# PCB_Calc.net
KiCad netlist of a schematic drawn in Altium Designer
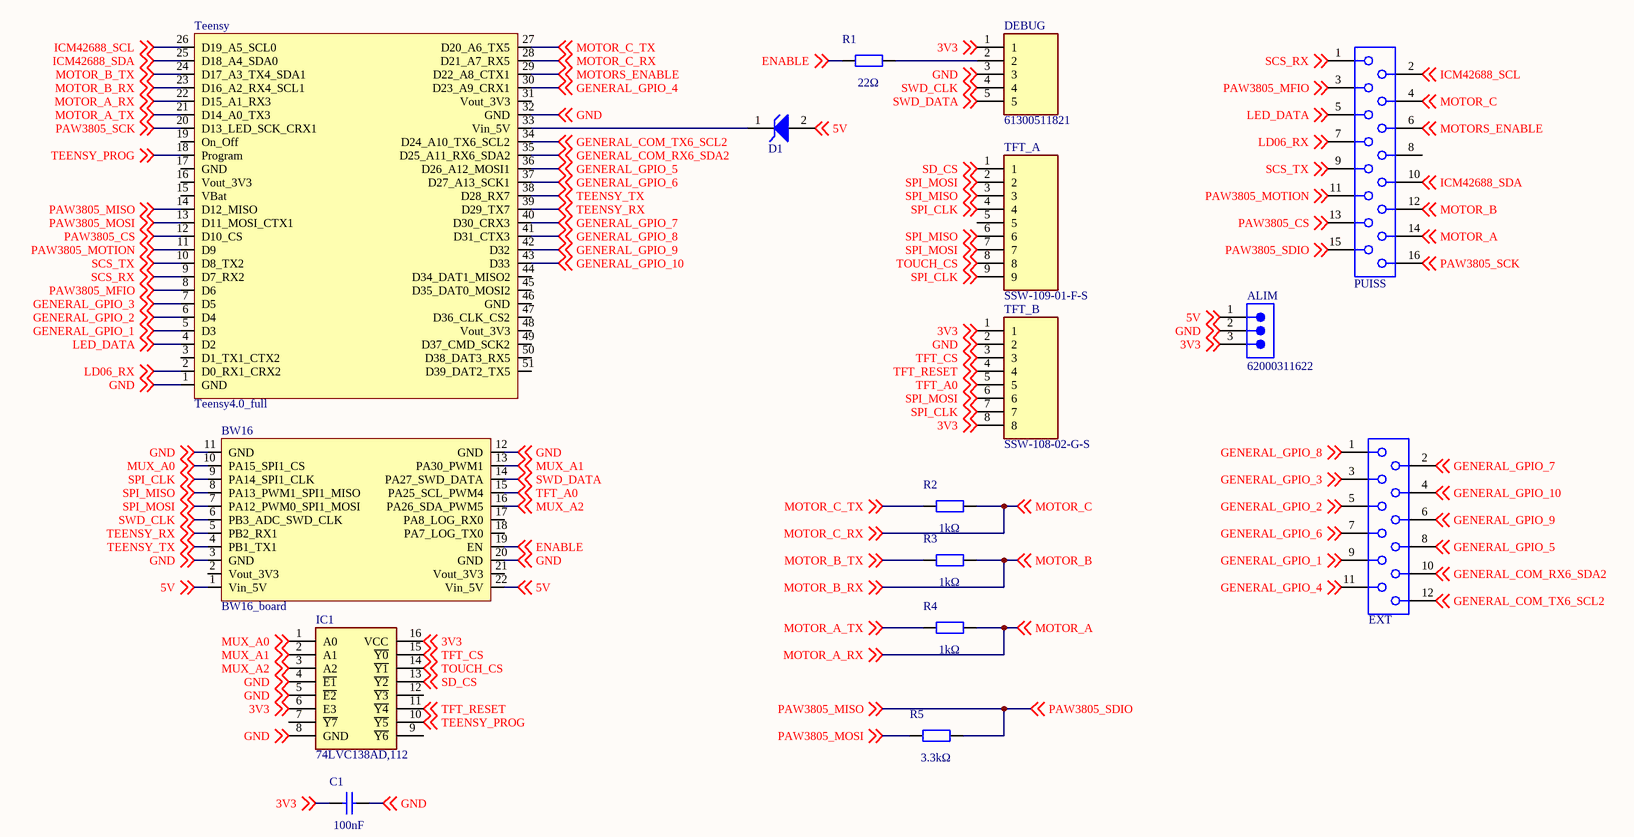
[diagram p0: PCB_Calc.SchDoc]

(export (version "E")
  (design (tool "Eeschema 10.0.6"))
  (components
    (comp (ref "ALIM")
      (value "62000311622")
      (footprint "62000311622")
      (description "WR-WTB Male Vertical Shrouded Header, pitch 2 mm, 3 pins")
      (fields (field (name "MANUFACTURER") "Wurth Elektronik"))
      (libsource (lib "Altium_WR-WTB (rev25b)") (part "62000311622"))
    )
    (comp (ref "BW16")
      (value "BW16_board")
      (footprint "BW16_board")
      (libsource (lib "SamacSys") (part "BW16_board"))
    )
    (comp (ref "C1")
      (value "100nF")
      (footprint "WCAP-CSGP_0603_L1.6W0.8H0.8_Reflow")
      (description "WCAP-CSGP Multilayer Ceramic Chip Capacitor, General Purpose, size 0603, 100nF, 16V")
      (fields
        (field (name "MANUFACTURER PART NUMBER") "885012206046")
        (field (name "MANUFACTURER") "Wurth Elektronik")
      )
      (libsource (lib "Altium_WCAP-CSGP (rev25c)") (part "885012206046"))
    )
    (comp (ref "D1")
      (value "400W, 5VDC")
      (footprint "WE-TVSP_DO-214AC_Unidirectional")
      (description "WE-TVSP SMT Power TVS Diode, DO-214AC, Unidirectional, 400W, 5VDC")
      (fields
        (field (name "MANUFACTURER PART NUMBER") "824500500")
        (field (name "MANUFACTURER") "Wurth Elektronik")
      )
      (libsource (lib "Altium_WE-TVSP (rev22b)") (part "824500500"))
    )
    (comp (ref "DEBUG")
      (value "61300511821")
      (footprint "SamacSys:61300511821")
      (description "Connector")
      (fields (field (name "MOUSER PART NUMBER") "710-61300511821"))
      (libsource (lib "*") (part "61300511821"))
    )
    (comp (ref "EXT")
      (value "690367181272")
      (footprint "690367181272")
      (fields (field (name "MANUFACTURER") "Wurth Elektronik"))
      (libsource (lib "Altium_WR-MM (rev22a)") (part "690367181272"))
    )
    (comp (ref "IC1")
      (value "74LVC138AD,112")
      (footprint "SamacSys:SOIC127P600X175-16N")
      (description "Integrated Circuit")
      (fields (field (name "MOUSER PART NUMBER") "771-LVC138AD112"))
      (libsource (lib "*") (part "74LVC138AD,112"))
    )
    (comp (ref "PUISS")
      (value "690367181672")
      (footprint "690367181672")
      (fields (field (name "MANUFACTURER") "Wurth Elektronik"))
      (libsource (lib "Altium_WR-MM (rev22a)") (part "690367181672"))
    )
    (comp (ref "R1")
      (value "22Ω")
      (footprint "WRIS-RSKS_0603_Reflow")
      (description "WRIS-RSKS Thick Film Resistor, size 0603, 22Ω, +/-5%, 100mW")
      (fields
        (field (name "MANUFACTURER PART NUMBER") "560112116043")
        (field (name "MANUFACTURER") "Wurth Elektronik")
      )
      (libsource (lib "Altium_WRIS-RSKS (rev25a)") (part "560112116043"))
    )
    (comp (ref "R2")
      (value "1kΩ")
      (footprint "WRIS-RSKS_0603_Reflow")
      (description "WRIS-RSKS Thick Film Resistor, size 0603, 1kΩ, +/-5%, 100mW")
      (fields
        (field (name "MANUFACTURER PART NUMBER") "560112116016")
        (field (name "MANUFACTURER") "Wurth Elektronik")
      )
      (libsource (lib "Altium_WRIS-RSKS (rev25a)") (part "560112116016"))
    )
    (comp (ref "R3")
      (value "1kΩ")
      (footprint "WRIS-RSKS_0603_Reflow")
      (description "WRIS-RSKS Thick Film Resistor, size 0603, 1kΩ, +/-5%, 100mW")
      (fields
        (field (name "MANUFACTURER PART NUMBER") "560112116016")
        (field (name "MANUFACTURER") "Wurth Elektronik")
      )
      (libsource (lib "Altium_WRIS-RSKS (rev25a)") (part "560112116016"))
    )
    (comp (ref "R4")
      (value "1kΩ")
      (footprint "WRIS-RSKS_0603_Reflow")
      (description "WRIS-RSKS Thick Film Resistor, size 0603, 1kΩ, +/-5%, 100mW")
      (fields
        (field (name "MANUFACTURER PART NUMBER") "560112116016")
        (field (name "MANUFACTURER") "Wurth Elektronik")
      )
      (libsource (lib "Altium_WRIS-RSKS (rev25a)") (part "560112116016"))
    )
    (comp (ref "R5")
      (value "3.3kΩ")
      (footprint "WRIS-RSKS_0603_Reflow")
      (description "WRIS-RSKS Thick Film Resistor, size 0603, 3.3kΩ, +/-1%, 100mW")
      (fields
        (field (name "MANUFACTURER PART NUMBER") "560112116047")
        (field (name "MANUFACTURER") "Wurth Elektronik")
      )
      (libsource (lib "Altium_WRIS-RSKS (rev25a)") (part "560112116047"))
    )
    (comp (ref "Teensy")
      (value "Teensy4.0_full")
      (footprint "Teensy4.0_full")
      (libsource (lib "SamacSys") (part "Teensy4.0_full"))
    )
    (comp (ref "TFT_A")
      (value "SSW-109-01-F-S")
      (footprint "SamacSys:61301015721")
      (description "Connector")
      (fields (field (name "MOUSER PART NUMBER") "200-SSW10901FS"))
      (libsource (lib "*") (part "SSW-109-01-F-S"))
    )
    (comp (ref "TFT_B")
      (value "SSW-108-02-G-S")
      (footprint "SamacSys:61300815721")
      (description "Connector")
      (fields (field (name "MOUSER PART NUMBER") "200-SSW10802GS"))
      (libsource (lib "*") (part "SSW-108-02-G-S"))
    )
  )
  (nets
    (net (code "1") (name "3V3") (class "Default")
      (node (ref "ALIM") (pin "3") (pinfunction "3_3") (pintype "passive"))
      (node (ref "C1") (pin "1") (pinfunction "1_1") (pintype "passive"))
      (node (ref "DEBUG") (pin "1") (pinfunction "1_1") (pintype "passive"))
      (node (ref "IC1") (pin "16") (pinfunction "VCC_16") (pintype "passive"))
      (node (ref "IC1") (pin "6") (pinfunction "E3_6") (pintype "passive"))
      (node (ref "TFT_B") (pin "1") (pinfunction "1_1") (pintype "passive"))
      (node (ref "TFT_B") (pin "8") (pinfunction "8_8") (pintype "passive"))
    )
    (net (code "2") (name "5V") (class "Default")
      (node (ref "ALIM") (pin "1") (pinfunction "1_1") (pintype "passive"))
      (node (ref "BW16") (pin "1") (pinfunction "Vin_5V_1") (pintype "passive"))
      (node (ref "BW16") (pin "22") (pinfunction "Vin_5V_22") (pintype "passive"))
      (node (ref "D1") (pin "2") (pinfunction "A_2") (pintype "passive"))
    )
    (net (code "3") (name "ENABLE") (class "Default")
      (node (ref "BW16") (pin "19") (pinfunction "EN_19") (pintype "passive"))
      (node (ref "R1") (pin "1") (pinfunction "1_1") (pintype "passive"))
    )
    (net (code "4") (name "GENERAL_COM_RX6_SDA2") (class "Default")
      (node (ref "EXT") (pin "10") (pinfunction "10_10") (pintype "passive"))
      (node (ref "Teensy") (pin "35") (pinfunction "D25_A11_RX6_SDA2_35") (pintype "passive"))
    )
    (net (code "5") (name "GENERAL_COM_TX6_SCL2") (class "Default")
      (node (ref "EXT") (pin "12") (pinfunction "12_12") (pintype "passive"))
      (node (ref "Teensy") (pin "34") (pinfunction "D24_A10_TX6_SCL2_34") (pintype "passive"))
    )
    (net (code "6") (name "GENERAL_GPIO_1") (class "Default")
      (node (ref "EXT") (pin "9") (pinfunction "9_9") (pintype "passive"))
      (node (ref "Teensy") (pin "5") (pinfunction "D3_5") (pintype "passive"))
    )
    (net (code "7") (name "GENERAL_GPIO_2") (class "Default")
      (node (ref "EXT") (pin "5") (pinfunction "5_5") (pintype "passive"))
      (node (ref "Teensy") (pin "6") (pinfunction "D4_6") (pintype "passive"))
    )
    (net (code "8") (name "GENERAL_GPIO_3") (class "Default")
      (node (ref "EXT") (pin "3") (pinfunction "3_3") (pintype "passive"))
      (node (ref "Teensy") (pin "7") (pinfunction "D5_7") (pintype "passive"))
    )
    (net (code "9") (name "GENERAL_GPIO_4") (class "Default")
      (node (ref "EXT") (pin "11") (pinfunction "11_11") (pintype "passive"))
      (node (ref "Teensy") (pin "30") (pinfunction "D23_A9_CRX1_30") (pintype "passive"))
    )
    (net (code "10") (name "GENERAL_GPIO_5") (class "Default")
      (node (ref "EXT") (pin "8") (pinfunction "8_8") (pintype "passive"))
      (node (ref "Teensy") (pin "36") (pinfunction "D26_A12_MOSI1_36") (pintype "passive"))
    )
    (net (code "11") (name "GENERAL_GPIO_6") (class "Default")
      (node (ref "EXT") (pin "7") (pinfunction "7_7") (pintype "passive"))
      (node (ref "Teensy") (pin "37") (pinfunction "D27_A13_SCK1_37") (pintype "passive"))
    )
    (net (code "12") (name "GENERAL_GPIO_7") (class "Default")
      (node (ref "EXT") (pin "2") (pinfunction "2_2") (pintype "passive"))
      (node (ref "Teensy") (pin "40") (pinfunction "D30_CRX3_40") (pintype "passive"))
    )
    (net (code "13") (name "GENERAL_GPIO_8") (class "Default")
      (node (ref "EXT") (pin "1") (pinfunction "1_1") (pintype "passive"))
      (node (ref "Teensy") (pin "41") (pinfunction "D31_CTX3_41") (pintype "passive"))
    )
    (net (code "14") (name "GENERAL_GPIO_9") (class "Default")
      (node (ref "EXT") (pin "6") (pinfunction "6_6") (pintype "passive"))
      (node (ref "Teensy") (pin "42") (pinfunction "D32_42") (pintype "passive"))
    )
    (net (code "15") (name "GENERAL_GPIO_10") (class "Default")
      (node (ref "EXT") (pin "4") (pinfunction "4_4") (pintype "passive"))
      (node (ref "Teensy") (pin "43") (pinfunction "D33_43") (pintype "passive"))
    )
    (net (code "16") (name "GND") (class "Default")
      (node (ref "ALIM") (pin "2") (pinfunction "2_2") (pintype "passive"))
      (node (ref "BW16") (pin "11") (pinfunction "GND_11") (pintype "passive"))
      (node (ref "BW16") (pin "12") (pinfunction "GND_12") (pintype "passive"))
      (node (ref "BW16") (pin "20") (pinfunction "GND_20") (pintype "passive"))
      (node (ref "BW16") (pin "3") (pinfunction "GND_3") (pintype "passive"))
      (node (ref "C1") (pin "2") (pinfunction "2_2") (pintype "passive"))
      (node (ref "DEBUG") (pin "3") (pinfunction "3_3") (pintype "passive"))
      (node (ref "IC1") (pin "4") (pinfunction "~{E1}_4") (pintype "passive"))
      (node (ref "IC1") (pin "5") (pinfunction "~{E2}_5") (pintype "passive"))
      (node (ref "IC1") (pin "8") (pinfunction "GND_8") (pintype "passive"))
      (node (ref "TFT_B") (pin "2") (pinfunction "2_2") (pintype "passive"))
      (node (ref "Teensy") (pin "1") (pinfunction "GND_1") (pintype "passive"))
      (node (ref "Teensy") (pin "32") (pinfunction "GND_32") (pintype "passive"))
    )
    (net (code "17") (name "ICM42688_SCL") (class "Default")
      (node (ref "PUISS") (pin "2") (pinfunction "2_2") (pintype "passive"))
      (node (ref "Teensy") (pin "26") (pinfunction "D19_A5_SCL0_26") (pintype "passive"))
    )
    (net (code "18") (name "ICM42688_SDA") (class "Default")
      (node (ref "PUISS") (pin "10") (pinfunction "10_10") (pintype "passive"))
      (node (ref "Teensy") (pin "25") (pinfunction "D18_A4_SDA0_25") (pintype "passive"))
    )
    (net (code "19") (name "LD06_RX") (class "Default")
      (node (ref "PUISS") (pin "7") (pinfunction "7_7") (pintype "passive"))
      (node (ref "Teensy") (pin "2") (pinfunction "D0_RX1_CRX2_2") (pintype "passive"))
    )
    (net (code "20") (name "LED_DATA") (class "Default")
      (node (ref "PUISS") (pin "5") (pinfunction "5_5") (pintype "passive"))
      (node (ref "Teensy") (pin "4") (pinfunction "D2_4") (pintype "passive"))
    )
    (net (code "21") (name "MOTORS_ENABLE") (class "Default")
      (node (ref "PUISS") (pin "6") (pinfunction "6_6") (pintype "passive"))
      (node (ref "Teensy") (pin "29") (pinfunction "D22_A8_CTX1_29") (pintype "passive"))
    )
    (net (code "22") (name "MOTOR_A") (class "Default")
      (node (ref "PUISS") (pin "14") (pinfunction "14_14") (pintype "passive"))
      (node (ref "R4") (pin "2") (pinfunction "2_2") (pintype "passive"))
      (node (ref "Teensy") (pin "22") (pinfunction "D15_A1_RX3_22") (pintype "passive"))
    )
    (net (code "23") (name "MOTOR_A_TX") (class "Default")
      (node (ref "R4") (pin "1") (pinfunction "1_1") (pintype "passive"))
      (node (ref "Teensy") (pin "21") (pinfunction "D14_A0_TX3_21") (pintype "passive"))
    )
    (net (code "24") (name "MOTOR_B") (class "Default")
      (node (ref "PUISS") (pin "12") (pinfunction "12_12") (pintype "passive"))
      (node (ref "R3") (pin "2") (pinfunction "2_2") (pintype "passive"))
      (node (ref "Teensy") (pin "23") (pinfunction "D16_A2_RX4_SCL1_23") (pintype "passive"))
    )
    (net (code "25") (name "MOTOR_B_TX") (class "Default")
      (node (ref "R3") (pin "1") (pinfunction "1_1") (pintype "passive"))
      (node (ref "Teensy") (pin "24") (pinfunction "D17_A3_TX4_SDA1_24") (pintype "passive"))
    )
    (net (code "26") (name "MOTOR_C") (class "Default")
      (node (ref "PUISS") (pin "4") (pinfunction "4_4") (pintype "passive"))
      (node (ref "R2") (pin "2") (pinfunction "2_2") (pintype "passive"))
      (node (ref "Teensy") (pin "28") (pinfunction "D21_A7_RX5_28") (pintype "passive"))
    )
    (net (code "27") (name "MOTOR_C_TX") (class "Default")
      (node (ref "R2") (pin "1") (pinfunction "1_1") (pintype "passive"))
      (node (ref "Teensy") (pin "27") (pinfunction "D20_A6_TX5_27") (pintype "passive"))
    )
    (net (code "28") (name "MUX_A0") (class "Default")
      (node (ref "BW16") (pin "10") (pinfunction "PA15_SPI1_CS_10") (pintype "passive"))
      (node (ref "IC1") (pin "1") (pinfunction "A0_1") (pintype "passive"))
    )
    (net (code "29") (name "MUX_A1") (class "Default")
      (node (ref "BW16") (pin "13") (pinfunction "PA30_PWM1_13") (pintype "passive"))
      (node (ref "IC1") (pin "2") (pinfunction "A1_2") (pintype "passive"))
    )
    (net (code "30") (name "MUX_A2") (class "Default")
      (node (ref "BW16") (pin "16") (pinfunction "PA26_SDA_PWM5_16") (pintype "passive"))
      (node (ref "IC1") (pin "3") (pinfunction "A2_3") (pintype "passive"))
    )
    (net (code "31") (name "Net-(D1-K)") (class "Default")
      (node (ref "D1") (pin "1") (pinfunction "K_1") (pintype "passive"))
      (node (ref "Teensy") (pin "33") (pinfunction "Vin_5V_33") (pintype "passive"))
    )
    (net (code "32") (name "Net-(DEBUG-Pad2)") (class "Default")
      (node (ref "DEBUG") (pin "2") (pinfunction "2_2") (pintype "passive"))
      (node (ref "R1") (pin "2") (pinfunction "2_2") (pintype "passive"))
    )
    (net (code "33") (name "PAW3805_CS") (class "Default")
      (node (ref "PUISS") (pin "13") (pinfunction "13_13") (pintype "passive"))
      (node (ref "Teensy") (pin "12") (pinfunction "D10_CS_12") (pintype "passive"))
    )
    (net (code "34") (name "PAW3805_MFIO") (class "Default")
      (node (ref "PUISS") (pin "3") (pinfunction "3_3") (pintype "passive"))
      (node (ref "Teensy") (pin "8") (pinfunction "D6_8") (pintype "passive"))
    )
    (net (code "35") (name "PAW3805_MISO") (class "Default")
      (node (ref "PUISS") (pin "15") (pinfunction "15_15") (pintype "passive"))
      (node (ref "R5") (pin "2") (pinfunction "2_2") (pintype "passive"))
      (node (ref "Teensy") (pin "14") (pinfunction "D12_MISO_14") (pintype "passive"))
    )
    (net (code "36") (name "PAW3805_MOSI") (class "Default")
      (node (ref "R5") (pin "1") (pinfunction "1_1") (pintype "passive"))
      (node (ref "Teensy") (pin "13") (pinfunction "D11_MOSI_CTX1_13") (pintype "passive"))
    )
    (net (code "37") (name "PAW3805_MOTION") (class "Default")
      (node (ref "PUISS") (pin "11") (pinfunction "11_11") (pintype "passive"))
      (node (ref "Teensy") (pin "11") (pinfunction "D9_11") (pintype "passive"))
    )
    (net (code "38") (name "PAW3805_SCK") (class "Default")
      (node (ref "PUISS") (pin "16") (pinfunction "16_16") (pintype "passive"))
      (node (ref "Teensy") (pin "20") (pinfunction "D13_LED_SCK_CRX1_20") (pintype "passive"))
    )
    (net (code "39") (name "SCS_RX") (class "Default")
      (node (ref "PUISS") (pin "1") (pinfunction "1_1") (pintype "passive"))
      (node (ref "Teensy") (pin "9") (pinfunction "D7_RX2_9") (pintype "passive"))
    )
    (net (code "40") (name "SCS_TX") (class "Default")
      (node (ref "PUISS") (pin "9") (pinfunction "9_9") (pintype "passive"))
      (node (ref "Teensy") (pin "10") (pinfunction "D8_TX2_10") (pintype "passive"))
    )
    (net (code "41") (name "SD_CS") (class "Default")
      (node (ref "IC1") (pin "13") (pinfunction "~{Y2}_13") (pintype "passive"))
      (node (ref "TFT_A") (pin "1") (pinfunction "1_1") (pintype "passive"))
    )
    (net (code "42") (name "SPI_CLK") (class "Default")
      (node (ref "BW16") (pin "9") (pinfunction "PA14_SPI1_CLK_9") (pintype "passive"))
      (node (ref "TFT_A") (pin "4") (pinfunction "4_4") (pintype "passive"))
      (node (ref "TFT_A") (pin "9") (pinfunction "9_9") (pintype "passive"))
      (node (ref "TFT_B") (pin "7") (pinfunction "7_7") (pintype "passive"))
    )
    (net (code "43") (name "SPI_MISO") (class "Default")
      (node (ref "BW16") (pin "8") (pinfunction "PA13_PWM1_SPI1_MISO_8") (pintype "passive"))
      (node (ref "TFT_A") (pin "3") (pinfunction "3_3") (pintype "passive"))
      (node (ref "TFT_A") (pin "6") (pinfunction "6_6") (pintype "passive"))
    )
    (net (code "44") (name "SPI_MOSI") (class "Default")
      (node (ref "BW16") (pin "7") (pinfunction "PA12_PWM0_SPI1_MOSI_7") (pintype "passive"))
      (node (ref "TFT_A") (pin "2") (pinfunction "2_2") (pintype "passive"))
      (node (ref "TFT_A") (pin "7") (pinfunction "7_7") (pintype "passive"))
      (node (ref "TFT_B") (pin "6") (pinfunction "6_6") (pintype "passive"))
    )
    (net (code "45") (name "SWD_CLK") (class "Default")
      (node (ref "BW16") (pin "6") (pinfunction "PB3_ADC_SWD_CLK_6") (pintype "passive"))
      (node (ref "DEBUG") (pin "4") (pinfunction "4_4") (pintype "passive"))
    )
    (net (code "46") (name "SWD_DATA") (class "Default")
      (node (ref "BW16") (pin "14") (pinfunction "PA27_SWD_DATA_14") (pintype "passive"))
      (node (ref "DEBUG") (pin "5") (pinfunction "5_5") (pintype "passive"))
    )
    (net (code "47") (name "TEENSY_PROG") (class "Default")
      (node (ref "IC1") (pin "10") (pinfunction "~{Y5}_10") (pintype "passive"))
      (node (ref "Teensy") (pin "18") (pinfunction "Program_18") (pintype "passive"))
    )
    (net (code "48") (name "TEENSY_RX") (class "Default")
      (node (ref "BW16") (pin "5") (pinfunction "PB2_RX1_5") (pintype "passive"))
      (node (ref "Teensy") (pin "39") (pinfunction "D29_TX7_39") (pintype "passive"))
    )
    (net (code "49") (name "TEENSY_TX") (class "Default")
      (node (ref "BW16") (pin "4") (pinfunction "PB1_TX1_4") (pintype "passive"))
      (node (ref "Teensy") (pin "38") (pinfunction "D28_RX7_38") (pintype "passive"))
    )
    (net (code "50") (name "TFT_A0") (class "Default")
      (node (ref "BW16") (pin "15") (pinfunction "PA25_SCL_PWM4_15") (pintype "passive"))
      (node (ref "TFT_B") (pin "5") (pinfunction "5_5") (pintype "passive"))
    )
    (net (code "51") (name "TFT_CS") (class "Default")
      (node (ref "IC1") (pin "15") (pinfunction "~{Y0}_15") (pintype "passive"))
      (node (ref "TFT_B") (pin "3") (pinfunction "3_3") (pintype "passive"))
    )
    (net (code "52") (name "TFT_RESET") (class "Default")
      (node (ref "IC1") (pin "11") (pinfunction "~{Y4}_11") (pintype "passive"))
      (node (ref "TFT_B") (pin "4") (pinfunction "4_4") (pintype "passive"))
    )
    (net (code "53") (name "TOUCH_CS") (class "Default")
      (node (ref "IC1") (pin "14") (pinfunction "~{Y1}_14") (pintype "passive"))
      (node (ref "TFT_A") (pin "8") (pinfunction "8_8") (pintype "passive"))
    )
    (net (code "54") (name "unconnected-(BW16-PA7_LOG_TX0-Pad18)") (class "Default")
      (node (ref "BW16") (pin "18") (pinfunction "PA7_LOG_TX0_18") (pintype "passive"))
    )
    (net (code "55") (name "unconnected-(BW16-PA8_LOG_RX0-Pad17)") (class "Default")
      (node (ref "BW16") (pin "17") (pinfunction "PA8_LOG_RX0_17") (pintype "passive"))
    )
    (net (code "56") (name "unconnected-(BW16-Vout_3V3-Pad2)") (class "Default")
      (node (ref "BW16") (pin "2") (pinfunction "Vout_3V3_2") (pintype "passive"))
    )
    (net (code "57") (name "unconnected-(BW16-Vout_3V3-Pad21)") (class "Default")
      (node (ref "BW16") (pin "21") (pinfunction "Vout_3V3_21") (pintype "passive"))
    )
    (net (code "58") (name "unconnected-(IC1-~{Y3}-Pad12)") (class "Default")
      (node (ref "IC1") (pin "12") (pinfunction "~{Y3}_12") (pintype "passive"))
    )
    (net (code "59") (name "unconnected-(IC1-~{Y6}-Pad9)") (class "Default")
      (node (ref "IC1") (pin "9") (pinfunction "~{Y6}_9") (pintype "passive"))
    )
    (net (code "60") (name "unconnected-(IC1-~{Y7}-Pad7)") (class "Default")
      (node (ref "IC1") (pin "7") (pinfunction "~{Y7}_7") (pintype "passive"))
    )
    (net (code "61") (name "unconnected-(PUISS-Pad8)") (class "Default")
      (node (ref "PUISS") (pin "8") (pinfunction "8_8") (pintype "passive"))
    )
    (net (code "62") (name "unconnected-(TFT_A-Pad5)") (class "Default")
      (node (ref "TFT_A") (pin "5") (pinfunction "5_5") (pintype "passive"))
    )
    (net (code "63") (name "unconnected-(Teensy-D1_TX1_CTX2-Pad3)") (class "Default")
      (node (ref "Teensy") (pin "3") (pinfunction "D1_TX1_CTX2_3") (pintype "passive"))
    )
    (net (code "64") (name "unconnected-(Teensy-D34_DAT1_MISO2-Pad44)") (class "Default")
      (node (ref "Teensy") (pin "44") (pinfunction "D34_DAT1_MISO2_44") (pintype "passive"))
    )
    (net (code "65") (name "unconnected-(Teensy-D35_DAT0_MOSI2-Pad45)") (class "Default")
      (node (ref "Teensy") (pin "45") (pinfunction "D35_DAT0_MOSI2_45") (pintype "passive"))
    )
    (net (code "66") (name "unconnected-(Teensy-D36_CLK_CS2-Pad47)") (class "Default")
      (node (ref "Teensy") (pin "47") (pinfunction "D36_CLK_CS2_47") (pintype "passive"))
    )
    (net (code "67") (name "unconnected-(Teensy-D37_CMD_SCK2-Pad49)") (class "Default")
      (node (ref "Teensy") (pin "49") (pinfunction "D37_CMD_SCK2_49") (pintype "passive"))
    )
    (net (code "68") (name "unconnected-(Teensy-D38_DAT3_RX5-Pad50)") (class "Default")
      (node (ref "Teensy") (pin "50") (pinfunction "D38_DAT3_RX5_50") (pintype "passive"))
    )
    (net (code "69") (name "unconnected-(Teensy-D39_DAT2_TX5-Pad51)") (class "Default")
      (node (ref "Teensy") (pin "51") (pinfunction "D39_DAT2_TX5_51") (pintype "passive"))
    )
    (net (code "70") (name "unconnected-(Teensy-GND-Pad17)") (class "Default")
      (node (ref "Teensy") (pin "17") (pinfunction "GND_17") (pintype "passive"))
    )
    (net (code "71") (name "unconnected-(Teensy-GND-Pad46)") (class "Default")
      (node (ref "Teensy") (pin "46") (pinfunction "GND_46") (pintype "passive"))
    )
    (net (code "72") (name "unconnected-(Teensy-On_Off-Pad19)") (class "Default")
      (node (ref "Teensy") (pin "19") (pinfunction "On_Off_19") (pintype "passive"))
    )
    (net (code "73") (name "unconnected-(Teensy-VBat-Pad15)") (class "Default")
      (node (ref "Teensy") (pin "15") (pinfunction "VBat_15") (pintype "passive"))
    )
    (net (code "74") (name "unconnected-(Teensy-Vout_3V3-Pad16)") (class "Default")
      (node (ref "Teensy") (pin "16") (pinfunction "Vout_3V3_16") (pintype "passive"))
    )
    (net (code "75") (name "unconnected-(Teensy-Vout_3V3-Pad31)") (class "Default")
      (node (ref "Teensy") (pin "31") (pinfunction "Vout_3V3_31") (pintype "passive"))
    )
    (net (code "76") (name "unconnected-(Teensy-Vout_3V3-Pad48)") (class "Default")
      (node (ref "Teensy") (pin "48") (pinfunction "Vout_3V3_48") (pintype "passive"))
    )
  )
)
